# Actuadores.net
KiCad netlist of a schematic drawn in Altium Designer
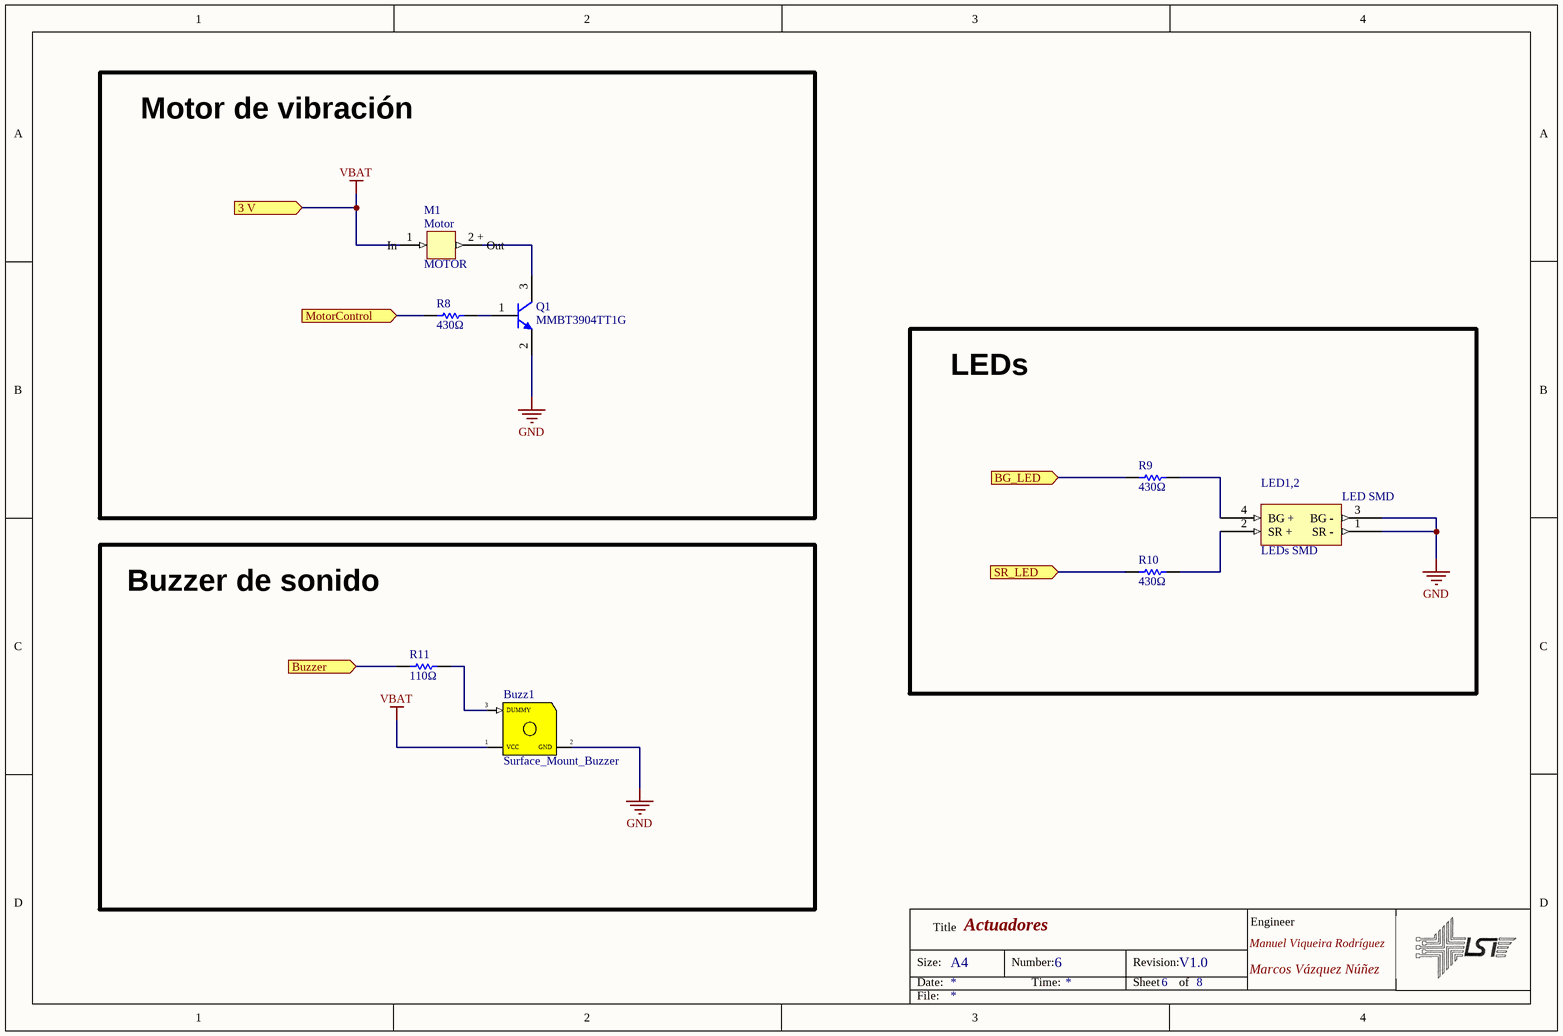
[diagram p0: Actuadores.SchDoc]

(export (version "E")
  (design (tool "Eeschema 10.0.6"))
  (components
    (comp (ref "Buzz1")
      (value "Surface_Mount_Buzzer")
      (footprint "buzzer")
      (libsource (lib "DEOP2021") (part "Surface_Mount_Buzzer"))
    )
    (comp (ref "LED1,2") (value "LEDs SMD") (footprint "LED_SMD") (libsource (lib "DEOP2021") (part "LED")))
    (comp (ref "M1") (value "MOTOR") (footprint "Motor") (libsource (lib "DEOP2021") (part "MOTOR")))
    (comp (ref "Q1")
      (value "MMBT3904TT1G")
      (footprint "ONSC-SC-75-3-463-01_V")
      (description "General Purpose Transistor, NPN Silicon, 3-Pin SC-75, Pb-Free, Tape and Reel")
      (fields (field (name "MANUFACTURER") "On Semiconductor"))
      (libsource (lib "Altium Content Vault") (part "ONSC-NPN-B1E2C3-3"))
    )
    (comp (ref "R8")
      (value "430Ω")
      (footprint "RESC1005X40X25NL05T10")
      (fields (field (name "PART NUMBER") "ERJ-U02F1501X") (field (name "MANUFACTURER") "Panasonic"))
      (libsource (lib "Altium Content Vault") (part "RES"))
    )
    (comp (ref "R9")
      (value "430Ω")
      (footprint "RESC1005X40X25NL05T10")
      (fields (field (name "PART NUMBER") "ERJ-U02F1501X") (field (name "MANUFACTURER") "Panasonic"))
      (libsource (lib "Altium Content Vault") (part "RES"))
    )
    (comp (ref "R10")
      (value "430Ω")
      (footprint "RESC1005X40X25NL05T10")
      (fields (field (name "PART NUMBER") "ERJ-U02F1501X") (field (name "MANUFACTURER") "Panasonic"))
      (libsource (lib "Altium Content Vault") (part "RES"))
    )
    (comp (ref "R11")
      (value "110Ω")
      (footprint "RESC1005X40X25NL05T10")
      (fields (field (name "PART NUMBER") "ERJ-U02F1501X") (field (name "MANUFACTURER") "Panasonic"))
      (libsource (lib "Altium Content Vault") (part "RES"))
    )
  )
  (nets
    (net (code "1") (name "/BG_LED") (class "Default")
      (node (ref "R9") (pin "1") (pinfunction "1_1") (pintype "passive"))
    )
    (net (code "2") (name "/Buzzer") (class "Default")
      (node (ref "R11") (pin "1") (pinfunction "1_1") (pintype "passive"))
    )
    (net (code "3") (name "/MotorControl") (class "Default")
      (node (ref "R8") (pin "1") (pinfunction "1_1") (pintype "passive"))
    )
    (net (code "4") (name "/SR_LED") (class "Default")
      (node (ref "R10") (pin "1") (pinfunction "1_1") (pintype "passive"))
    )
    (net (code "5") (name "GND") (class "Default")
      (node (ref "Buzz1") (pin "2") (pinfunction "GND_2") (pintype "power_in"))
      (node (ref "LED1,2") (pin "1") (pinfunction "SR_-_1") (pintype "output"))
      (node (ref "LED1,2") (pin "3") (pinfunction "BG_-_3") (pintype "output"))
      (node (ref "Q1") (pin "2") (pinfunction "E_2") (pintype "passive"))
    )
    (net (code "6") (name "Net-(Buzz1-DUMMY)") (class "Default")
      (node (ref "Buzz1") (pin "3") (pinfunction "DUMMY_3") (pintype "input"))
      (node (ref "R11") (pin "2") (pinfunction "2_2") (pintype "passive"))
    )
    (net (code "7") (name "Net-(LED1,2-BG_+)") (class "Default")
      (node (ref "LED1,2") (pin "4") (pinfunction "BG_+_4") (pintype "input"))
      (node (ref "R9") (pin "2") (pinfunction "2_2") (pintype "passive"))
    )
    (net (code "8") (name "Net-(LED1,2-SR_+)") (class "Default")
      (node (ref "LED1,2") (pin "2") (pinfunction "SR_+_2") (pintype "input"))
      (node (ref "R10") (pin "2") (pinfunction "2_2") (pintype "passive"))
    )
    (net (code "9") (name "Net-(M1-Out)") (class "Default")
      (node (ref "M1") (pin "2_+") (pinfunction "Out_2_+") (pintype "output"))
      (node (ref "Q1") (pin "3") (pinfunction "C_3") (pintype "passive"))
    )
    (net (code "10") (name "Net-(Q1-B)") (class "Default")
      (node (ref "Q1") (pin "1") (pinfunction "B_1") (pintype "passive"))
      (node (ref "R8") (pin "2") (pinfunction "2_2") (pintype "passive"))
    )
    (net (code "11") (name "VBAT") (class "Default")
      (node (ref "Buzz1") (pin "1") (pinfunction "VCC_1") (pintype "power_in"))
      (node (ref "M1") (pin "1") (pinfunction "In_1") (pintype "input"))
    )
  )
)
